# POE_UART_hall_crossboard_1_1.net
KiCad netlist of a schematic drawn in Altium Designer
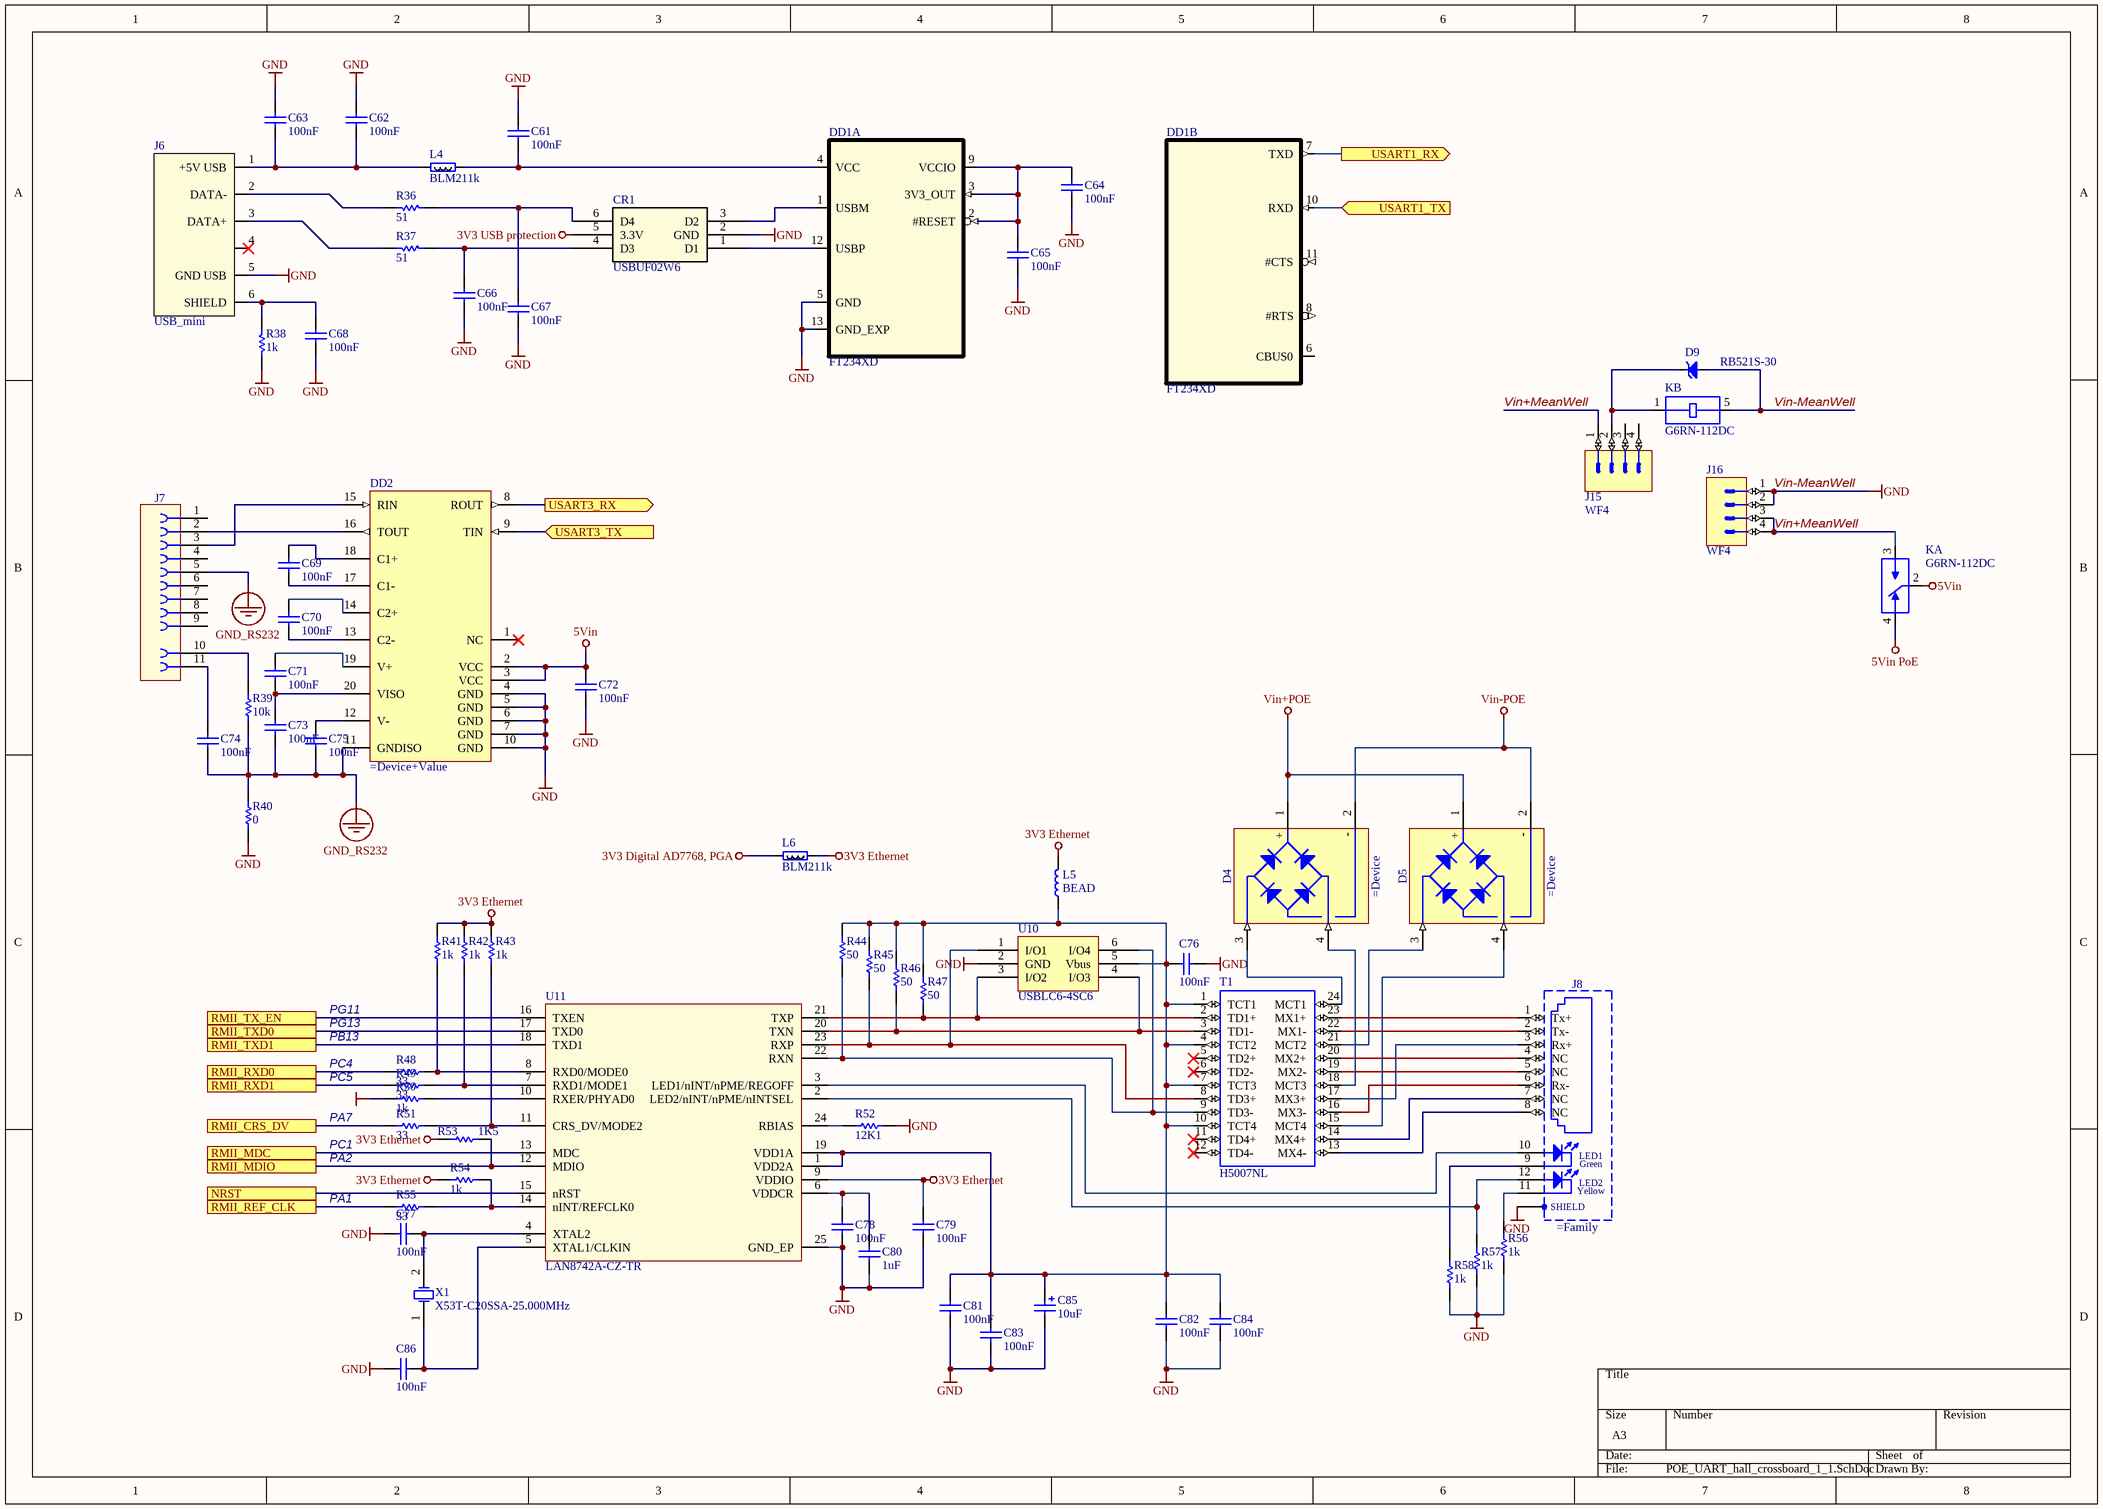
[diagram p0: POE_UART_hall_crossboard_1_1.SchDoc]

(export (version "E")
  (design (tool "Eeschema 10.0.6"))
  (components
    (comp (ref "C61")
      (value "100nF")
      (footprint "hall_crossboard_1_1_library:0603C")
      (description "Capacitor 0402 / 0603 / 0805")
      (libsource (lib "hall_crossboard_1_1_library") (part "Capacitor_ST"))
    )
    (comp (ref "C62")
      (value "100nF")
      (footprint "hall_crossboard_1_1_library:0603C")
      (description "Capacitor 0402 / 0603 / 0805")
      (libsource (lib "hall_crossboard_1_1_library") (part "Capacitor_ST"))
    )
    (comp (ref "C63")
      (value "100nF")
      (footprint "hall_crossboard_1_1_library:0603C")
      (description "Capacitor 0402 / 0603 / 0805")
      (libsource (lib "hall_crossboard_1_1_library") (part "Capacitor_ST"))
    )
    (comp (ref "C64")
      (value "100nF")
      (footprint "hall_crossboard_1_1_library:0603C")
      (description "Capacitor 0402 / 0603 / 0805")
      (libsource (lib "hall_crossboard_1_1_library") (part "Capacitor_ST"))
    )
    (comp (ref "C65")
      (value "100nF")
      (footprint "hall_crossboard_1_1_library:0603C")
      (description "Capacitor 0402 / 0603 / 0805")
      (libsource (lib "hall_crossboard_1_1_library") (part "Capacitor_ST"))
    )
    (comp (ref "C66")
      (value "100nF")
      (footprint "hall_crossboard_1_1_library:0603C")
      (description "Capacitor 0402 / 0603 / 0805")
      (libsource (lib "hall_crossboard_1_1_library") (part "Capacitor_ST"))
    )
    (comp (ref "C67")
      (value "100nF")
      (footprint "hall_crossboard_1_1_library:0603C")
      (description "Capacitor 0402 / 0603 / 0805")
      (libsource (lib "hall_crossboard_1_1_library") (part "Capacitor_ST"))
    )
    (comp (ref "C68")
      (value "100nF")
      (footprint "hall_crossboard_1_1_library:0603C")
      (description "Capacitor 0402 / 0603 / 0805")
      (libsource (lib "hall_crossboard_1_1_library") (part "Capacitor_ST"))
    )
    (comp (ref "C69")
      (value "100nF")
      (footprint "hall_crossboard_1_1_library:0603C")
      (description "Capacitor 0402 / 0603 / 0805")
      (libsource (lib "hall_crossboard_1_1_library") (part "Capacitor_ST"))
    )
    (comp (ref "C70")
      (value "100nF")
      (footprint "hall_crossboard_1_1_library:0603C")
      (description "Capacitor 0402 / 0603 / 0805")
      (libsource (lib "hall_crossboard_1_1_library") (part "Capacitor_ST"))
    )
    (comp (ref "C71")
      (value "100nF")
      (footprint "hall_crossboard_1_1_library:0603C")
      (description "Capacitor 0402 / 0603 / 0805")
      (libsource (lib "hall_crossboard_1_1_library") (part "Capacitor_ST"))
    )
    (comp (ref "C72")
      (value "100nF")
      (footprint "hall_crossboard_1_1_library:0603C")
      (description "Capacitor 0402 / 0603 / 0805")
      (libsource (lib "hall_crossboard_1_1_library") (part "Capacitor_ST"))
    )
    (comp (ref "C73")
      (value "100nF")
      (footprint "hall_crossboard_1_1_library:0603C")
      (description "Capacitor 0402 / 0603 / 0805")
      (libsource (lib "hall_crossboard_1_1_library") (part "Capacitor_ST"))
    )
    (comp (ref "C74")
      (value "100nF")
      (footprint "hall_crossboard_1_1_library:0603C")
      (description "Capacitor 0402 / 0603 / 0805")
      (libsource (lib "hall_crossboard_1_1_library") (part "Capacitor_ST"))
    )
    (comp (ref "C75")
      (value "100nF")
      (footprint "hall_crossboard_1_1_library:0603C")
      (description "Capacitor 0402 / 0603 / 0805")
      (libsource (lib "hall_crossboard_1_1_library") (part "Capacitor_ST"))
    )
    (comp (ref "C76")
      (value "100nF")
      (footprint "hall_crossboard_1_1_library:0603C")
      (description "Capacitor 0402 / 0603 / 0805")
      (libsource (lib "schematic_hall_crossboard_1_1_library") (part "Capacitor_ST"))
    )
    (comp (ref "C77")
      (value "100nF")
      (footprint "hall_crossboard_1_1_library:0603C")
      (description "Capacitor 0402 / 0603 / 0805")
      (libsource (lib "schematic_hall_crossboard_1_1_library") (part "Capacitor_ST"))
    )
    (comp (ref "C78")
      (value "100nF")
      (footprint "hall_crossboard_1_1_library:0603C")
      (description "Capacitor 0402 / 0603 / 0805")
      (libsource (lib "schematic_hall_crossboard_1_1_library") (part "Capacitor_ST"))
    )
    (comp (ref "C79")
      (value "100nF")
      (footprint "hall_crossboard_1_1_library:0603C")
      (description "Capacitor 0402 / 0603 / 0805")
      (libsource (lib "schematic_hall_crossboard_1_1_library") (part "Capacitor_ST"))
    )
    (comp (ref "C80")
      (value "1uF")
      (footprint "hall_crossboard_1_1_library:0805C")
      (description "Capacitor 0402 / 0603 / 0805")
      (libsource (lib "hall_crossboard_1_1_library") (part "Capacitor_ST"))
    )
    (comp (ref "C81")
      (value "100nF")
      (footprint "hall_crossboard_1_1_library:0603C")
      (description "Capacitor 0402 / 0603 / 0805")
      (libsource (lib "schematic_hall_crossboard_1_1_library") (part "Capacitor_ST"))
    )
    (comp (ref "C82")
      (value "100nF")
      (footprint "hall_crossboard_1_1_library:0603C")
      (description "Capacitor 0402 / 0603 / 0805")
      (libsource (lib "schematic_hall_crossboard_1_1_library") (part "Capacitor_ST"))
    )
    (comp (ref "C83")
      (value "100nF")
      (footprint "hall_crossboard_1_1_library:0603C")
      (description "Capacitor 0402 / 0603 / 0805")
      (libsource (lib "schematic_hall_crossboard_1_1_library") (part "Capacitor_ST"))
    )
    (comp (ref "C84")
      (value "100nF")
      (footprint "hall_crossboard_1_1_library:0603C")
      (description "Capacitor 0402 / 0603 / 0805")
      (libsource (lib "schematic_hall_crossboard_1_1_library") (part "Capacitor_ST"))
    )
    (comp (ref "C85")
      (value "10uF")
      (footprint "hall_crossboard_1_1_library:0805C")
      (description "Polarized Capacitor,10uF,10V,10%,typeA,VISHAY")
      (libsource (lib "schematic_hall_crossboard_1_1_library") (part "Cap_10uF_POL_10%_TANA"))
    )
    (comp (ref "C86")
      (value "100nF")
      (footprint "hall_crossboard_1_1_library:0603C")
      (description "Capacitor 0402 / 0603 / 0805")
      (libsource (lib "schematic_hall_crossboard_1_1_library") (part "Capacitor_ST"))
    )
    (comp (ref "CR1")
      (value "USBUF02W6")
      (footprint "footprint_hall_crossboard_1_1_library:SOTT323-6L_STM-M")
      (description "USB protection")
      (libsource (lib "schematic_hall_crossboard_1_1_library") (part "USBUF02W6"))
    )
    (comp (ref "D4")
      (value "~")
      (description "Bridge Rectifier 1+ 2AC 3- 4AC")
      (libsource (lib "hall_crossboard_1_1_library") (part "Bridge Rectifier 1+ 2AC 3- 4AC"))
    )
    (comp (ref "D5")
      (value "~")
      (description "Bridge Rectifier 1+ 2AC 3- 4AC")
      (libsource (lib "hall_crossboard_1_1_library") (part "Bridge Rectifier 1+ 2AC 3- 4AC"))
    )
    (comp (ref "D9")
      (value "RB521S-30")
      (footprint "hall_crossboard_1_1_library:SODFL1608X65N")
      (description "Чип Шоттки диод")
      (fields (field (name "VOLTAGE") "30V"))
      (libsource (lib "DDSintLib") (part "RB521S-30"))
    )
    (comp (ref "DD1")
      (value "FT234XD")
      (footprint "footprint_hall_crossboard_1_1_library:DFN_12-045")
      (description "USB-UART driver")
      (libsource (lib "schematic_hall_crossboard_1_1_library") (part "FT234XD"))
    )
    (comp (ref "DD2")
      (value "ADM3251")
      (footprint "footprint_hall_library:SOIC127P1032X265-20N")
      (description "Driver UART-RS232")
      (libsource (lib "schematic_hall_crossboard_1_1_library") (part "ADM3251"))
    )
    (comp (ref "J6")
      (value "USB_mini")
      (footprint "footprint_hall_crossboard_1_1_library:TYCO_1734035-1")
      (description "Вилка  PLS 6x2.54")
      (libsource (lib "schematic_hall_crossboard_1_1_library") (part "USB_mini"))
    )
    (comp (ref "J7")
      (value "~")
      (footprint "footprint_hall_library:TYCO_5747844-5")
      (description "Connector 9 Female")
      (libsource (lib "schematic_hall_crossboard_1_1_library") (part "Connector 9 Female"))
    )
    (comp (ref "J8")
      (value "~")
      (footprint "AMPHENOL_RJHSE-5381")
      (description "1 Port, 8 Positions, CAT5 RJ45 Modular Connector With Yellow And Green LEDs")
      (libsource (lib "hall_crossboard_1_1_library") (part "AMPHENOL_RJHSE-5381"))
    )
    (comp (ref "J15")
      (value "WF4")
      (footprint "hall_crossboard_1_1_library:WF4_2_54")
      (description "Вилка  WF4")
      (libsource (lib "") (part "WF4_1"))
    )
    (comp (ref "J16")
      (value "WF4")
      (footprint "hall_crossboard_1_1_library:WF4_2_54")
      (description "Вилка  WF4")
      (libsource (lib "schematic_hall_crossboard_1_1_library") (part "WF4"))
    )
    (comp (ref "K")
      (value "G6RN-112DC")
      (footprint "footprint_hall_crossboard_1_1_library:RELAY_G6RN-1_12DC")
      (description "General Purpose Relay SPST-NO _1 Form A_ 12VDC Coil Through Hole")
      (fields (field (name "MF") "Omron Electronics") (field (name "MP") "G6RN-1 12DC"))
      (libsource (lib "schematic_hall_crossboard_1_1_library") (part "G6RN-112DC"))
    )
    (comp (ref "L4")
      (value "BLM211k")
      (footprint "footprint_hall_crossboard_1_1_library:RESC2012X50N")
      (description "SMD Ferrite bead 0805")
      (libsource (lib "schematic_hall_crossboard_1_1_library") (part "BLM21"))
    )
    (comp (ref "L5")
      (value "BEAD")
      (footprint "footprint_hall_crossboard_1_1_library:0603L")
      (description "Inductor")
      (fields (field (name "PUBLISHER") "Altium Limited"))
      (libsource (lib "schematic_hall_crossboard_1_1_library") (part "Inductor"))
    )
    (comp (ref "L6")
      (value "BLM211k")
      (footprint "footprint_hall_crossboard_1_1_library:RESC2012X50N")
      (description "SMD Ferrite bead 0805")
      (libsource (lib "schematic_hall_crossboard_1_1_library") (part "BLM21"))
    )
    (comp (ref "R36")
      (value "51")
      (footprint "0603R")
      (description "Resistor 0402 / 0603 / 0805")
      (libsource (lib "hall_crossboard_1_1_library") (part "Resistor_ST"))
    )
    (comp (ref "R37")
      (value "51")
      (footprint "0603R")
      (description "Resistor 0402 / 0603 / 0805")
      (libsource (lib "hall_crossboard_1_1_library") (part "Resistor_ST"))
    )
    (comp (ref "R38")
      (value "1k")
      (footprint "0603R")
      (description "Resistor 0402 / 0603 / 0805")
      (libsource (lib "hall_crossboard_1_1_library") (part "Resistor_ST"))
    )
    (comp (ref "R39")
      (value "10k")
      (footprint "0603R")
      (description "Resistor")
      (fields (field (name "PUBLISHER") "Altium Limited"))
      (libsource (lib "hall_crossboard_1_1_library") (part "Res1"))
    )
    (comp (ref "R40")
      (value "0")
      (footprint "0603R")
      (description "Resistor 0402 / 0603 / 0805")
      (libsource (lib "hall_crossboard_1_1_library") (part "Resistor_ST"))
    )
    (comp (ref "R41")
      (value "1k")
      (footprint "0603R")
      (description "Resistor 0402 / 0603 / 0805")
      (libsource (lib "hall_crossboard_1_1_library") (part "Resistor_ST"))
    )
    (comp (ref "R42")
      (value "1k")
      (footprint "0603R")
      (description "Resistor 0402 / 0603 / 0805")
      (libsource (lib "hall_crossboard_1_1_library") (part "Resistor_ST"))
    )
    (comp (ref "R43")
      (value "1k")
      (footprint "0603R")
      (description "Resistor 0402 / 0603 / 0805")
      (libsource (lib "hall_crossboard_1_1_library") (part "Resistor_ST"))
    )
    (comp (ref "R44")
      (value "50")
      (footprint "0603R")
      (description "Resistor 0402 / 0603 / 0805")
      (libsource (lib "hall_crossboard_1_1_library") (part "Resistor_ST"))
    )
    (comp (ref "R45")
      (value "50")
      (footprint "0603R")
      (description "Resistor 0402 / 0603 / 0805")
      (libsource (lib "hall_crossboard_1_1_library") (part "Resistor_ST"))
    )
    (comp (ref "R46")
      (value "50")
      (footprint "0603R")
      (description "Resistor 0402 / 0603 / 0805")
      (libsource (lib "hall_crossboard_1_1_library") (part "Resistor_ST"))
    )
    (comp (ref "R47")
      (value "50")
      (footprint "0603R")
      (description "Resistor 0402 / 0603 / 0805")
      (libsource (lib "hall_crossboard_1_1_library") (part "Resistor_ST"))
    )
    (comp (ref "R48")
      (value "33")
      (footprint "0603R")
      (description "Resistor 0402 / 0603 / 0805")
      (libsource (lib "hall_crossboard_1_1_library") (part "Resistor_ST"))
    )
    (comp (ref "R49")
      (value "33")
      (footprint "0603R")
      (description "Resistor 0402 / 0603 / 0805")
      (libsource (lib "hall_crossboard_1_1_library") (part "Resistor_ST"))
    )
    (comp (ref "R50")
      (value "1k")
      (footprint "0603R")
      (description "Resistor 0402 / 0603 / 0805")
      (libsource (lib "hall_crossboard_1_1_library") (part "Resistor_ST"))
    )
    (comp (ref "R51")
      (value "33")
      (footprint "0603R")
      (description "Resistor 0402 / 0603 / 0805")
      (libsource (lib "hall_crossboard_1_1_library") (part "Resistor_ST"))
    )
    (comp (ref "R52")
      (value "12K1")
      (footprint "0603R")
      (description "Resistor 0402 / 0603 / 0805")
      (libsource (lib "hall_crossboard_1_1_library") (part "Resistor_ST"))
    )
    (comp (ref "R53")
      (value "1K5")
      (footprint "0603R")
      (description "Resistor,1K5,0402,1%,YAGEO")
      (libsource (lib "MCD_TOOLS") (part "Res_1K5_1%_0402"))
    )
    (comp (ref "R54")
      (value "1k")
      (footprint "0603R")
      (description "Resistor 0402 / 0603 / 0805")
      (libsource (lib "hall_crossboard_1_1_library") (part "Resistor_ST"))
    )
    (comp (ref "R55")
      (value "33")
      (footprint "0603R")
      (description "Resistor 0402 / 0603 / 0805")
      (libsource (lib "hall_crossboard_1_1_library") (part "Resistor_ST"))
    )
    (comp (ref "R56")
      (value "1k")
      (footprint "0603R")
      (description "Resistor 0402 / 0603 / 0805")
      (libsource (lib "hall_crossboard_1_1_library") (part "Resistor_ST"))
    )
    (comp (ref "R57")
      (value "1k")
      (footprint "0603R")
      (description "Resistor 0402 / 0603 / 0805")
      (libsource (lib "hall_crossboard_1_1_library") (part "Resistor_ST"))
    )
    (comp (ref "R58")
      (value "1k")
      (footprint "0603R")
      (description "Resistor 0402 / 0603 / 0805")
      (libsource (lib "hall_crossboard_1_1_library") (part "Resistor_ST"))
    )
    (comp (ref "T1")
      (value "H5007NL")
      (footprint "footprint_hall_crossboard_1_1_library:SOIC127P1600X551-24N")
      (description "Isolation and Data Interface _Encapsulated_ Pulse Transformer 1CT:1CT Surface Mount")
      (fields (field (name "MP") "H5007NL-T") (field (name "MF") "Pulse Electronics"))
      (libsource (lib "schematic_hall_crossboard_1_1_library") (part "H5007NL"))
    )
    (comp (ref "U10")
      (value "USBLC6-4SC6")
      (footprint "hall_crossboard_1_1_library:SOT23-6L")
      (libsource (lib "schematic_hall_crossboard_1_1_library") (part "USBLC6-4SC6"))
    )
    (comp (ref "U11")
      (value "LAN8742A-CZ-TR")
      (footprint "hall_crossboard_1_1_library:QFN24_0R5_4X4")
      (libsource (lib "schematic_hall_crossboard_1_1_library") (part "LAN8742A-CZ-TR"))
    )
    (comp (ref "X1")
      (value "X53T-C20SSA-25.000MHz")
      (footprint "XTAL_2SM_5R0X3R2")
      (description "Crystal Oscillator")
      (fields (field (name "PUBLISHER") "Altium Limited"))
      (libsource (lib "MB1137") (part "XTAL_5032"))
    )
  )
  (nets
    (net (code "1") (name "/NRST") (class "Default")
      (node (ref "U11") (pin "15") (pinfunction "nRST_15") (pintype "passive"))
    )
    (net (code "2") (name "/RMII_CRS_DV") (class "Default")
      (node (ref "R51") (pin "1") (pinfunction "1_1") (pintype "passive"))
    )
    (net (code "3") (name "/RMII_MDC") (class "Default")
      (node (ref "U11") (pin "13") (pinfunction "MDC_13") (pintype "passive"))
    )
    (net (code "4") (name "/RMII_MDIO") (class "Default")
      (node (ref "R53") (pin "1") (pinfunction "1_1") (pintype "passive"))
      (node (ref "U11") (pin "12") (pinfunction "MDIO_12") (pintype "passive"))
    )
    (net (code "5") (name "/RMII_REF_CLK") (class "Default")
      (node (ref "R55") (pin "1") (pinfunction "1_1") (pintype "passive"))
    )
    (net (code "6") (name "/RMII_RXD0") (class "Default")
      (node (ref "R48") (pin "1") (pinfunction "1_1") (pintype "passive"))
    )
    (net (code "7") (name "/RMII_RXD1") (class "Default")
      (node (ref "R49") (pin "1") (pinfunction "1_1") (pintype "passive"))
    )
    (net (code "8") (name "/RMII_TXD0") (class "Default")
      (node (ref "U11") (pin "17") (pinfunction "TXD0_17") (pintype "passive"))
    )
    (net (code "9") (name "/RMII_TXD1") (class "Default")
      (node (ref "U11") (pin "18") (pinfunction "TXD1_18") (pintype "passive"))
    )
    (net (code "10") (name "/RMII_TX_EN") (class "Default")
      (node (ref "U11") (pin "16") (pinfunction "TXEN_16") (pintype "passive"))
    )
    (net (code "11") (name "/USART1_RX") (class "Default")
      (node (ref "DD1") (pin "7") (pinfunction "TXD_7") (pintype "output"))
    )
    (net (code "12") (name "/USART1_TX") (class "Default")
      (node (ref "DD1") (pin "10") (pinfunction "RXD_10") (pintype "input"))
    )
    (net (code "13") (name "/USART3_RX") (class "Default")
      (node (ref "DD2") (pin "8") (pinfunction "ROUT_8") (pintype "output"))
    )
    (net (code "14") (name "/USART3_TX") (class "Default")
      (node (ref "DD2") (pin "9") (pinfunction "TIN_9") (pintype "input"))
    )
    (net (code "15") (name "/Vin+MeanWell") (class "Default")
      (node (ref "J15") (pin "1") (pinfunction "1_1") (pintype "bidirectional"))
      (node (ref "J16") (pin "3") (pinfunction "3_3") (pintype "bidirectional"))
      (node (ref "J16") (pin "4") (pinfunction "4_4") (pintype "bidirectional"))
      (node (ref "K") (pin "3") (pinfunction "NO_3") (pintype "passive"))
    )
    (net (code "16") (name "3V3 Digital AD7768, PGA") (class "Default")
      (node (ref "L6") (pin "2") (pinfunction "2_2") (pintype "passive"))
    )
    (net (code "17") (name "3V3 Ethernet") (class "Default")
      (node (ref "C79") (pin "2") (pinfunction "2_2") (pintype "passive"))
      (node (ref "L5") (pin "2") (pinfunction "2_2") (pintype "passive"))
      (node (ref "L6") (pin "1") (pinfunction "1_1") (pintype "passive"))
      (node (ref "R41") (pin "2") (pinfunction "2_2") (pintype "passive"))
      (node (ref "R42") (pin "2") (pinfunction "2_2") (pintype "passive"))
      (node (ref "R43") (pin "2") (pinfunction "2_2") (pintype "passive"))
      (node (ref "R53") (pin "2") (pinfunction "2_2") (pintype "passive"))
      (node (ref "R54") (pin "1") (pinfunction "1_1") (pintype "passive"))
      (node (ref "U11") (pin "9") (pinfunction "VDDIO_9") (pintype "passive"))
    )
    (net (code "18") (name "3V3 USB protection") (class "Default")
      (node (ref "CR1") (pin "5") (pinfunction "3.3V_5") (pintype "passive"))
    )
    (net (code "19") (name "5Vin") (class "Default")
      (node (ref "C72") (pin "2") (pinfunction "2_2") (pintype "passive"))
      (node (ref "DD2") (pin "2") (pinfunction "VCC_2") (pintype "power_in"))
      (node (ref "DD2") (pin "3") (pinfunction "VCC_3") (pintype "power_in"))
      (node (ref "K") (pin "2") (pinfunction "COM_2") (pintype "passive"))
    )
    (net (code "20") (name "5Vin PoE") (class "Default")
      (node (ref "K") (pin "4") (pinfunction "NC_4") (pintype "passive"))
    )
    (net (code "21") (name "GND") (class "Default")
      (node (ref "C61") (pin "2") (pinfunction "2_2") (pintype "passive"))
      (node (ref "C62") (pin "2") (pinfunction "2_2") (pintype "passive"))
      (node (ref "C63") (pin "2") (pinfunction "2_2") (pintype "passive"))
      (node (ref "C64") (pin "1") (pinfunction "1_1") (pintype "passive"))
      (node (ref "C65") (pin "1") (pinfunction "1_1") (pintype "passive"))
      (node (ref "C66") (pin "2") (pinfunction "2_2") (pintype "passive"))
      (node (ref "C67") (pin "1") (pinfunction "1_1") (pintype "passive"))
      (node (ref "C68") (pin "1") (pinfunction "1_1") (pintype "passive"))
      (node (ref "C72") (pin "1") (pinfunction "1_1") (pintype "passive"))
      (node (ref "C76") (pin "1") (pinfunction "1_1") (pintype "passive"))
      (node (ref "C77") (pin "2") (pinfunction "2_2") (pintype "passive"))
      (node (ref "C78") (pin "1") (pinfunction "1_1") (pintype "passive"))
      (node (ref "C79") (pin "1") (pinfunction "1_1") (pintype "passive"))
      (node (ref "C80") (pin "1") (pinfunction "1_1") (pintype "passive"))
      (node (ref "C81") (pin "1") (pinfunction "1_1") (pintype "passive"))
      (node (ref "C82") (pin "1") (pinfunction "1_1") (pintype "passive"))
      (node (ref "C83") (pin "1") (pinfunction "1_1") (pintype "passive"))
      (node (ref "C84") (pin "1") (pinfunction "1_1") (pintype "passive"))
      (node (ref "C85") (pin "2") (pinfunction "2_2") (pintype "passive"))
      (node (ref "C86") (pin "2") (pinfunction "2_2") (pintype "passive"))
      (node (ref "CR1") (pin "2") (pinfunction "GND_2") (pintype "power_in"))
      (node (ref "D9") (pin "2") (pinfunction "A_2") (pintype "passive"))
      (node (ref "DD1") (pin "13") (pinfunction "GND_EXP_13") (pintype "power_in"))
      (node (ref "DD1") (pin "5") (pinfunction "GND_5") (pintype "power_in"))
      (node (ref "DD2") (pin "10") (pinfunction "GND_10") (pintype "power_in"))
      (node (ref "DD2") (pin "4") (pinfunction "GND_4") (pintype "power_in"))
      (node (ref "DD2") (pin "5") (pinfunction "GND_5") (pintype "power_in"))
      (node (ref "DD2") (pin "6") (pinfunction "GND_6") (pintype "power_in"))
      (node (ref "DD2") (pin "7") (pinfunction "GND_7") (pintype "power_in"))
      (node (ref "J16") (pin "1") (pinfunction "1_1") (pintype "bidirectional"))
      (node (ref "J16") (pin "2") (pinfunction "2_2") (pintype "bidirectional"))
      (node (ref "J6") (pin "5") (pinfunction "GND_USB_5") (pintype "passive"))
      (node (ref "J8") (pin "SHIELD") (pinfunction "SHIELD_SHIELD") (pintype "passive"))
      (node (ref "K") (pin "5") (pinfunction "COIL2_5") (pintype "passive"))
      (node (ref "R38") (pin "1") (pinfunction "1_1") (pintype "passive"))
      (node (ref "R40") (pin "2") (pinfunction "2_2") (pintype "passive"))
      (node (ref "R50") (pin "1") (pinfunction "1_1") (pintype "passive"))
      (node (ref "R52") (pin "2") (pinfunction "2_2") (pintype "passive"))
      (node (ref "R56") (pin "1") (pinfunction "1_1") (pintype "passive"))
      (node (ref "R57") (pin "1") (pinfunction "1_1") (pintype "passive"))
      (node (ref "R58") (pin "1") (pinfunction "1_1") (pintype "passive"))
      (node (ref "U10") (pin "2") (pinfunction "GND_2") (pintype "passive"))
      (node (ref "U11") (pin "25") (pinfunction "GND_EP_25") (pintype "passive"))
    )
    (net (code "22") (name "GND_RS232") (class "Default")
      (node (ref "C73") (pin "1") (pinfunction "1_1") (pintype "passive"))
      (node (ref "C74") (pin "1") (pinfunction "1_1") (pintype "passive"))
      (node (ref "C75") (pin "1") (pinfunction "1_1") (pintype "passive"))
      (node (ref "DD2") (pin "11") (pinfunction "GNDISO_11") (pintype "power_in"))
      (node (ref "J7") (pin "5") (pinfunction "5_5") (pintype "passive"))
      (node (ref "R39") (pin "2") (pinfunction "2_2") (pintype "passive"))
      (node (ref "R40") (pin "1") (pinfunction "1_1") (pintype "passive"))
    )
    (net (code "23") (name "Net-(C74-Pad2)") (class "Default")
      (node (ref "C74") (pin "2") (pinfunction "2_2") (pintype "passive"))
      (node (ref "J7") (pin "11") (pinfunction "11_11") (pintype "passive"))
    )
    (net (code "24") (name "Net-(CR1-D1)") (class "Default")
      (node (ref "CR1") (pin "1") (pinfunction "D1_1") (pintype "passive"))
      (node (ref "DD1") (pin "12") (pinfunction "USBP_12") (pintype "bidirectional"))
    )
    (net (code "25") (name "Net-(CR1-D2)") (class "Default")
      (node (ref "CR1") (pin "3") (pinfunction "D2_3") (pintype "passive"))
      (node (ref "DD1") (pin "1") (pinfunction "USBM_1") (pintype "bidirectional"))
    )
    (net (code "26") (name "Net-(CR1-D3)") (class "Default")
      (node (ref "C66") (pin "1") (pinfunction "1_1") (pintype "passive"))
      (node (ref "CR1") (pin "4") (pinfunction "D3_4") (pintype "passive"))
      (node (ref "R37") (pin "1") (pinfunction "1_1") (pintype "passive"))
    )
    (net (code "27") (name "Net-(CR1-D4)") (class "Default")
      (node (ref "C67") (pin "2") (pinfunction "2_2") (pintype "passive"))
      (node (ref "CR1") (pin "6") (pinfunction "D4_6") (pintype "passive"))
      (node (ref "R36") (pin "1") (pinfunction "1_1") (pintype "passive"))
    )
    (net (code "28") (name "Net-(D9-C)") (class "Default")
      (node (ref "D9") (pin "1") (pinfunction "C_1") (pintype "passive"))
      (node (ref "J15") (pin "2") (pinfunction "2_2") (pintype "bidirectional"))
      (node (ref "K") (pin "1") (pinfunction "COIL1_1") (pintype "passive"))
    )
    (net (code "29") (name "Net-(DD1A-#RESET)") (class "Default")
      (node (ref "C64") (pin "2") (pinfunction "2_2") (pintype "passive"))
      (node (ref "C65") (pin "2") (pinfunction "2_2") (pintype "passive"))
      (node (ref "DD1") (pin "2") (pinfunction "#RESET_2") (pintype "input"))
      (node (ref "DD1") (pin "3") (pinfunction "3V3_OUT_3") (pintype "input"))
      (node (ref "DD1") (pin "9") (pinfunction "VCCIO_9") (pintype "power_in"))
    )
    (net (code "30") (name "Net-(DD1A-VCC)") (class "Default")
      (node (ref "C61") (pin "1") (pinfunction "1_1") (pintype "passive"))
      (node (ref "DD1") (pin "4") (pinfunction "VCC_4") (pintype "power_in"))
      (node (ref "L4") (pin "1") (pinfunction "1_1") (pintype "passive"))
    )
    (net (code "31") (name "Net-(DD2-C1+)") (class "Default")
      (node (ref "C69") (pin "2") (pinfunction "2_2") (pintype "passive"))
      (node (ref "DD2") (pin "18") (pinfunction "C1+_18") (pintype "passive"))
    )
    (net (code "32") (name "Net-(DD2-C1-)") (class "Default")
      (node (ref "C69") (pin "1") (pinfunction "1_1") (pintype "passive"))
      (node (ref "DD2") (pin "17") (pinfunction "C1-_17") (pintype "passive"))
    )
    (net (code "33") (name "Net-(DD2-C2+)") (class "Default")
      (node (ref "C70") (pin "2") (pinfunction "2_2") (pintype "passive"))
      (node (ref "DD2") (pin "14") (pinfunction "C2+_14") (pintype "passive"))
    )
    (net (code "34") (name "Net-(DD2-C2-)") (class "Default")
      (node (ref "C70") (pin "1") (pinfunction "1_1") (pintype "passive"))
      (node (ref "DD2") (pin "13") (pinfunction "C2-_13") (pintype "passive"))
    )
    (net (code "35") (name "Net-(DD2-RIN)") (class "Default")
      (node (ref "DD2") (pin "15") (pinfunction "RIN_15") (pintype "input"))
      (node (ref "J7") (pin "3") (pinfunction "3_3") (pintype "passive"))
    )
    (net (code "36") (name "Net-(DD2-TOUT)") (class "Default")
      (node (ref "DD2") (pin "16") (pinfunction "TOUT_16") (pintype "output"))
      (node (ref "J7") (pin "2") (pinfunction "2_2") (pintype "passive"))
    )
    (net (code "37") (name "Net-(DD2-V+)") (class "Default")
      (node (ref "C71") (pin "2") (pinfunction "2_2") (pintype "passive"))
      (node (ref "DD2") (pin "19") (pinfunction "V+_19") (pintype "power_in"))
    )
    (net (code "38") (name "Net-(DD2-V-)") (class "Default")
      (node (ref "C75") (pin "2") (pinfunction "2_2") (pintype "passive"))
      (node (ref "DD2") (pin "12") (pinfunction "V-_12") (pintype "power_in"))
    )
    (net (code "39") (name "Net-(DD2-VISO)") (class "Default")
      (node (ref "C71") (pin "1") (pinfunction "1_1") (pintype "passive"))
      (node (ref "C73") (pin "2") (pinfunction "2_2") (pintype "passive"))
      (node (ref "DD2") (pin "20") (pinfunction "VISO_20") (pintype "power_in"))
    )
    (net (code "40") (name "Net-(J6-+5V_USB)") (class "Default")
      (node (ref "C62") (pin "1") (pinfunction "1_1") (pintype "passive"))
      (node (ref "C63") (pin "1") (pinfunction "1_1") (pintype "passive"))
      (node (ref "J6") (pin "1") (pinfunction "+5V_USB_1") (pintype "passive"))
      (node (ref "L4") (pin "2") (pinfunction "2_2") (pintype "passive"))
    )
    (net (code "41") (name "Net-(J6-DATA+)") (class "Default")
      (node (ref "J6") (pin "3") (pinfunction "DATA+_3") (pintype "passive"))
      (node (ref "R37") (pin "2") (pinfunction "2_2") (pintype "passive"))
    )
    (net (code "42") (name "Net-(J6-DATA-)") (class "Default")
      (node (ref "J6") (pin "2") (pinfunction "DATA-_2") (pintype "passive"))
      (node (ref "R36") (pin "2") (pinfunction "2_2") (pintype "passive"))
    )
    (net (code "43") (name "Net-(J6-SHIELD)") (class "Default")
      (node (ref "C68") (pin "2") (pinfunction "2_2") (pintype "passive"))
      (node (ref "J6") (pin "6") (pinfunction "SHIELD_6") (pintype "passive"))
      (node (ref "R38") (pin "2") (pinfunction "2_2") (pintype "passive"))
    )
    (net (code "44") (name "Net-(J7-Pad10)") (class "Default")
      (node (ref "J7") (pin "10") (pinfunction "10_10") (pintype "passive"))
      (node (ref "R39") (pin "1") (pinfunction "1_1") (pintype "passive"))
    )
    (net (code "45") (name "Net-(J8-ALED1)") (class "Default")
      (node (ref "J8") (pin "10") (pinfunction "ALED1_10") (pintype "passive"))
      (node (ref "U11") (pin "3") (pinfunction "LED1/nINT/nPME/REGOFF_3") (pintype "passive"))
    )
    (net (code "46") (name "Net-(J8-ALED2)") (class "Default")
      (node (ref "J8") (pin "11") (pinfunction "ALED2_11") (pintype "passive"))
      (node (ref "R56") (pin "2") (pinfunction "2_2") (pintype "passive"))
    )
    (net (code "47") (name "Net-(J8-CLED1)") (class "Default")
      (node (ref "J8") (pin "9") (pinfunction "CLED1_9") (pintype "passive"))
      (node (ref "R58") (pin "2") (pinfunction "2_2") (pintype "passive"))
    )
    (net (code "48") (name "Net-(J8-CLED2)") (class "Default")
      (node (ref "J8") (pin "12") (pinfunction "CLED2_12") (pintype "passive"))
      (node (ref "R57") (pin "2") (pinfunction "2_2") (pintype "passive"))
      (node (ref "U11") (pin "2") (pinfunction "LED2/nINT/nPME/nINTSEL_2") (pintype "passive"))
    )
    (net (code "49") (name "Net-(J8-Rx+)") (class "Default")
      (node (ref "J8") (pin "3") (pinfunction "Rx+_3") (pintype "bidirectional"))
      (node (ref "T1") (pin "17") (pinfunction "MX3+_17") (pintype "bidirectional"))
    )
    (net (code "50") (name "Net-(J8-Rx-)") (class "Default")
      (node (ref "J8") (pin "6") (pinfunction "Rx-_6") (pintype "bidirectional"))
      (node (ref "T1") (pin "16") (pinfunction "MX3-_16") (pintype "bidirectional"))
    )
    (net (code "51") (name "Net-(J8-Tx+)") (class "Default")
      (node (ref "J8") (pin "1") (pinfunction "Tx+_1") (pintype "bidirectional"))
      (node (ref "T1") (pin "23") (pinfunction "MX1+_23") (pintype "bidirectional"))
    )
    (net (code "52") (name "Net-(J8-Tx-)") (class "Default")
      (node (ref "J8") (pin "2") (pinfunction "Tx-_2") (pintype "bidirectional"))
      (node (ref "T1") (pin "22") (pinfunction "MX1-_22") (pintype "bidirectional"))
    )
    (net (code "53") (name "Net-(T1-MCT1)") (class "Default")
      (node (ref "D4") (pin "3") (pinfunction "AC_3") (pintype "input"))
      (node (ref "T1") (pin "24") (pinfunction "MCT1_24") (pintype "bidirectional"))
    )
    (net (code "54") (name "Net-(T1-MCT2)") (class "Default")
      (node (ref "D5") (pin "3") (pinfunction "AC_3") (pintype "input"))
      (node (ref "T1") (pin "21") (pinfunction "MCT2_21") (pintype "bidirectional"))
    )
    (net (code "55") (name "Net-(T1-MCT3)") (class "Default")
      (node (ref "D4") (pin "4") (pinfunction "AC_4") (pintype "input"))
      (node (ref "T1") (pin "18") (pinfunction "MCT3_18") (pintype "bidirectional"))
    )
    (net (code "56") (name "Net-(T1-MCT4)") (class "Default")
      (node (ref "D5") (pin "4") (pinfunction "AC_4") (pintype "input"))
      (node (ref "T1") (pin "15") (pinfunction "MCT4_15") (pintype "bidirectional"))
    )
    (net (code "57") (name "Net-(T1-MX2+)") (class "Default")
      (node (ref "J8") (pin "4") (pinfunction "NC_4") (pintype "bidirectional"))
      (node (ref "T1") (pin "20") (pinfunction "MX2+_20") (pintype "bidirectional"))
    )
    (net (code "58") (name "Net-(T1-MX2-)") (class "Default")
      (node (ref "J8") (pin "5") (pinfunction "NC_5") (pintype "bidirectional"))
      (node (ref "T1") (pin "19") (pinfunction "MX2-_19") (pintype "bidirectional"))
    )
    (net (code "59") (name "Net-(T1-MX4+)") (class "Default")
      (node (ref "J8") (pin "7") (pinfunction "NC_7") (pintype "bidirectional"))
      (node (ref "T1") (pin "14") (pinfunction "MX4+_14") (pintype "bidirectional"))
    )
    (net (code "60") (name "Net-(T1-MX4-)") (class "Default")
      (node (ref "J8") (pin "8") (pinfunction "NC_8") (pintype "bidirectional"))
      (node (ref "T1") (pin "13") (pinfunction "MX4-_13") (pintype "bidirectional"))
    )
    (net (code "61") (name "Net-(T1-TCT1)") (class "Default")
      (node (ref "C76") (pin "2") (pinfunction "2_2") (pintype "passive"))
      (node (ref "C81") (pin "2") (pinfunction "2_2") (pintype "passive"))
      (node (ref "C82") (pin "2") (pinfunction "2_2") (pintype "passive"))
      (node (ref "C83") (pin "2") (pinfunction "2_2") (pintype "passive"))
      (node (ref "C84") (pin "2") (pinfunction "2_2") (pintype "passive"))
      (node (ref "C85") (pin "1") (pinfunction "1_1") (pintype "passive"))
      (node (ref "L5") (pin "1") (pinfunction "1_1") (pintype "passive"))
      (node (ref "R44") (pin "2") (pinfunction "2_2") (pintype "passive"))
      (node (ref "R45") (pin "2") (pinfunction "2_2") (pintype "passive"))
      (node (ref "R46") (pin "2") (pinfunction "2_2") (pintype "passive"))
      (node (ref "R47") (pin "2") (pinfunction "2_2") (pintype "passive"))
      (node (ref "T1") (pin "1") (pinfunction "TCT1_1") (pintype "bidirectional"))
      (node (ref "T1") (pin "10") (pinfunction "TCT4_10") (pintype "bidirectional"))
      (node (ref "T1") (pin "4") (pinfunction "TCT2_4") (pintype "bidirectional"))
      (node (ref "T1") (pin "7") (pinfunction "TCT3_7") (pintype "bidirectional"))
      (node (ref "U10") (pin "5") (pinfunction "Vbus_5") (pintype "passive"))
      (node (ref "U11") (pin "1") (pinfunction "VDD2A_1") (pintype "passive"))
      (node (ref "U11") (pin "19") (pinfunction "VDD1A_19") (pintype "passive"))
    )
    (net (code "62") (name "Net-(T1-TD1+)") (class "Default")
      (node (ref "R47") (pin "1") (pinfunction "1_1") (pintype "passive"))
      (node (ref "T1") (pin "2") (pinfunction "TD1+_2") (pintype "bidirectional"))
      (node (ref "U10") (pin "3") (pinfunction "I/O2_3") (pintype "passive"))
      (node (ref "U11") (pin "21") (pinfunction "TXP_21") (pintype "passive"))
    )
    (net (code "63") (name "Net-(T1-TD1-)") (class "Default")
      (node (ref "R46") (pin "1") (pinfunction "1_1") (pintype "passive"))
      (node (ref "T1") (pin "3") (pinfunction "TD1-_3") (pintype "bidirectional"))
      (node (ref "U10") (pin "4") (pinfunction "I/O3_4") (pintype "passive"))
      (node (ref "U11") (pin "20") (pinfunction "TXN_20") (pintype "passive"))
    )
    (net (code "64") (name "Net-(T1-TD3+)") (class "Default")
      (node (ref "R45") (pin "1") (pinfunction "1_1") (pintype "passive"))
      (node (ref "T1") (pin "8") (pinfunction "TD3+_8") (pintype "bidirectional"))
      (node (ref "U10") (pin "1") (pinfunction "I/O1_1") (pintype "passive"))
      (node (ref "U11") (pin "23") (pinfunction "RXP_23") (pintype "passive"))
    )
    (net (code "65") (name "Net-(T1-TD3-)") (class "Default")
      (node (ref "R44") (pin "1") (pinfunction "1_1") (pintype "passive"))
      (node (ref "T1") (pin "9") (pinfunction "TD3-_9") (pintype "bidirectional"))
      (node (ref "U10") (pin "6") (pinfunction "I/O4_6") (pintype "passive"))
      (node (ref "U11") (pin "22") (pinfunction "RXN_22") (pintype "passive"))
    )
    (net (code "66") (name "Net-(U11-CRS_DV{slash}MODE2)") (class "Default")
      (node (ref "R43") (pin "1") (pinfunction "1_1") (pintype "passive"))
      (node (ref "R51") (pin "2") (pinfunction "2_2") (pintype "passive"))
      (node (ref "U11") (pin "11") (pinfunction "CRS_DV/MODE2_11") (pintype "passive"))
    )
    (net (code "67") (name "Net-(U11-RBIAS)") (class "Default")
      (node (ref "R52") (pin "1") (pinfunction "1_1") (pintype "passive"))
      (node (ref "U11") (pin "24") (pinfunction "RBIAS_24") (pintype "passive"))
    )
    (net (code "68") (name "Net-(U11-RXD0{slash}MODE0)") (class "Default")
      (node (ref "R41") (pin "1") (pinfunction "1_1") (pintype "passive"))
      (node (ref "R48") (pin "2") (pinfunction "2_2") (pintype "passive"))
      (node (ref "U11") (pin "8") (pinfunction "RXD0/MODE0_8") (pintype "passive"))
    )
    (net (code "69") (name "Net-(U11-RXD1{slash}MODE1)") (class "Default")
      (node (ref "R42") (pin "1") (pinfunction "1_1") (pintype "passive"))
      (node (ref "R49") (pin "2") (pinfunction "2_2") (pintype "passive"))
      (node (ref "U11") (pin "7") (pinfunction "RXD1/MODE1_7") (pintype "passive"))
    )
    (net (code "70") (name "Net-(U11-RXER{slash}PHYAD0)") (class "Default")
      (node (ref "R50") (pin "2") (pinfunction "2_2") (pintype "passive"))
      (node (ref "U11") (pin "10") (pinfunction "RXER/PHYAD0_10") (pintype "passive"))
    )
    (net (code "71") (name "Net-(U11-VDDCR)") (class "Default")
      (node (ref "C78") (pin "2") (pinfunction "2_2") (pintype "passive"))
      (node (ref "C80") (pin "2") (pinfunction "2_2") (pintype "passive"))
      (node (ref "U11") (pin "6") (pinfunction "VDDCR_6") (pintype "passive"))
    )
    (net (code "72") (name "Net-(U11-XTAL1{slash}CLKIN)") (class "Default")
      (node (ref "C86") (pin "1") (pinfunction "1_1") (pintype "passive"))
      (node (ref "U11") (pin "5") (pinfunction "XTAL1/CLKIN_5") (pintype "passive"))
      (node (ref "X1") (pin "1") (pinfunction "OSC1_1") (pintype "passive"))
    )
    (net (code "73") (name "Net-(U11-XTAL2)") (class "Default")
      (node (ref "C77") (pin "1") (pinfunction "1_1") (pintype "passive"))
      (node (ref "U11") (pin "4") (pinfunction "XTAL2_4") (pintype "passive"))
      (node (ref "X1") (pin "2") (pinfunction "OSC2_2") (pintype "passive"))
    )
    (net (code "74") (name "Net-(U11-nINT{slash}REFCLK0)") (class "Default")
      (node (ref "R54") (pin "2") (pinfunction "2_2") (pintype "passive"))
      (node (ref "R55") (pin "2") (pinfunction "2_2") (pintype "passive"))
      (node (ref "U11") (pin "14") (pinfunction "nINT/REFCLK0_14") (pintype "passive"))
    )
    (net (code "75") (name "Vin+POE") (class "Default")
      (node (ref "D4") (pin "1") (pinfunction "+_1") (pintype "power_in"))
      (node (ref "D5") (pin "1") (pinfunction "+_1") (pintype "power_in"))
    )
    (net (code "76") (name "Vin-POE") (class "Default")
      (node (ref "D4") (pin "2") (pinfunction "-_2") (pintype "power_in"))
      (node (ref "D5") (pin "2") (pinfunction "-_2") (pintype "power_in"))
    )
    (net (code "77") (name "unconnected-(DD1B-#CTS-Pad11)") (class "Default")
      (node (ref "DD1") (pin "11") (pinfunction "#CTS_11") (pintype "input"))
    )
    (net (code "78") (name "unconnected-(DD1B-#RTS-Pad8)") (class "Default")
      (node (ref "DD1") (pin "8") (pinfunction "#RTS_8") (pintype "output"))
    )
    (net (code "79") (name "unconnected-(DD1B-CBUS0-Pad6)") (class "Default")
      (node (ref "DD1") (pin "6") (pinfunction "CBUS0_6") (pintype "bidirectional"))
    )
    (net (code "80") (name "unconnected-(DD2-NC-Pad1)") (class "Default")
      (node (ref "DD2") (pin "1") (pinfunction "NC_1") (pintype "passive+no_connect"))
    )
    (net (code "81") (name "unconnected-(J6-Pad4)") (class "Default")
      (node (ref "J6") (pin "4") (pinfunction "4_4") (pintype "passive+no_connect"))
    )
    (net (code "82") (name "unconnected-(J7-Pad1)") (class "Default")
      (node (ref "J7") (pin "1") (pinfunction "1_1") (pintype "passive"))
    )
    (net (code "83") (name "unconnected-(J7-Pad4)") (class "Default")
      (node (ref "J7") (pin "4") (pinfunction "4_4") (pintype "passive"))
    )
    (net (code "84") (name "unconnected-(J7-Pad6)") (class "Default")
      (node (ref "J7") (pin "6") (pinfunction "6_6") (pintype "passive"))
    )
    (net (code "85") (name "unconnected-(J7-Pad7)") (class "Default")
      (node (ref "J7") (pin "7") (pinfunction "7_7") (pintype "passive"))
    )
    (net (code "86") (name "unconnected-(J7-Pad8)") (class "Default")
      (node (ref "J7") (pin "8") (pinfunction "8_8") (pintype "passive"))
    )
    (net (code "87") (name "unconnected-(J7-Pad9)") (class "Default")
      (node (ref "J7") (pin "9") (pinfunction "9_9") (pintype "passive"))
    )
    (net (code "88") (name "unconnected-(J15-Pad3)") (class "Default")
      (node (ref "J15") (pin "3") (pinfunction "3_3") (pintype "bidirectional"))
    )
    (net (code "89") (name "unconnected-(J15-Pad4)") (class "Default")
      (node (ref "J15") (pin "4") (pinfunction "4_4") (pintype "bidirectional"))
    )
    (net (code "90") (name "unconnected-(T1-TD2+-Pad5)") (class "Default")
      (node (ref "T1") (pin "5") (pinfunction "TD2+_5") (pintype "bidirectional+no_connect"))
    )
    (net (code "91") (name "unconnected-(T1-TD2--Pad6)") (class "Default")
      (node (ref "T1") (pin "6") (pinfunction "TD2-_6") (pintype "bidirectional+no_connect"))
    )
    (net (code "92") (name "unconnected-(T1-TD4+-Pad11)") (class "Default")
      (node (ref "T1") (pin "11") (pinfunction "TD4+_11") (pintype "bidirectional+no_connect"))
    )
    (net (code "93") (name "unconnected-(T1-TD4--Pad12)") (class "Default")
      (node (ref "T1") (pin "12") (pinfunction "TD4-_12") (pintype "bidirectional+no_connect"))
    )
  )
)
